# schema_projet_mai_juin_gamestation.net
KiCad netlist of a schematic drawn in Altium Designer
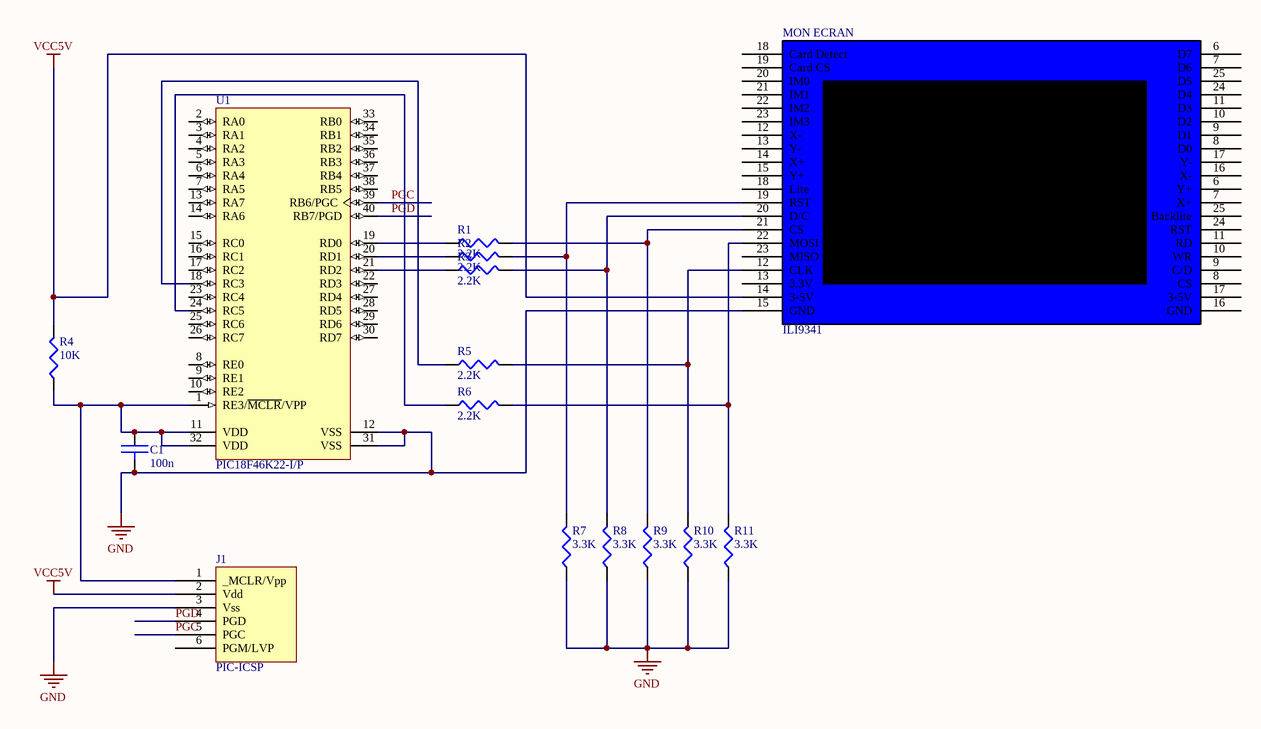
[diagram p0: schema_projet_mai_juin_gamestation.SchDoc]

(export (version "E")
  (design (tool "Eeschema 10.0.6"))
  (components
    (comp (ref "C1")
      (value "100n")
      (footprint "0402")
      (description "capacité non polarisée")
      (fields (field (name "Comment") "CAP"))
      (libsource (lib "ISEN_basics_15-02-2023") (part "CAP"))
    )
    (comp (ref "J1")
      (value "PIC-ICSP")
      (footprint "PIC-ICSP")
      (libsource (lib "ISEN_basics_15-02-2023") (part "PIC-ICSP"))
    )
    (comp (ref "MON ECRAN")
      (value "ILI9341")
      (libsource (lib "schema_ecran_ILI9341_Adafruit") (part "Component_1"))
    )
    (comp (ref "R1")
      (value "2.2K")
      (footprint "0201")
      (description "resistance")
      (fields (field (name "Comment") "RES"))
      (libsource (lib "ISEN_basics_15-02-2023") (part "RES"))
    )
    (comp (ref "R2")
      (value "2.2K")
      (footprint "0201")
      (description "resistance")
      (fields (field (name "Comment") "RES"))
      (libsource (lib "ISEN_basics_15-02-2023") (part "RES"))
    )
    (comp (ref "R3")
      (value "2.2K")
      (footprint "0201")
      (description "resistance")
      (fields (field (name "Comment") "RES"))
      (libsource (lib "ISEN_basics_15-02-2023") (part "RES"))
    )
    (comp (ref "R4")
      (value "10K")
      (footprint "0201")
      (description "resistance")
      (fields (field (name "Comment") "RES"))
      (libsource (lib "ISEN_basics_15-02-2023") (part "RES"))
    )
    (comp (ref "R5")
      (value "2.2K")
      (footprint "0201")
      (description "resistance")
      (fields (field (name "Comment") "RES"))
      (libsource (lib "ISEN_basics_15-02-2023") (part "RES"))
    )
    (comp (ref "R6")
      (value "2.2K")
      (footprint "0201")
      (description "resistance")
      (fields (field (name "Comment") "RES"))
      (libsource (lib "ISEN_basics_15-02-2023") (part "RES"))
    )
    (comp (ref "R7")
      (value "3.3K")
      (footprint "0201")
      (description "resistance")
      (fields (field (name "Comment") "RES"))
      (libsource (lib "ISEN_basics_15-02-2023") (part "RES"))
    )
    (comp (ref "R8")
      (value "3.3K")
      (footprint "0201")
      (description "resistance")
      (fields (field (name "Comment") "RES"))
      (libsource (lib "ISEN_basics_15-02-2023") (part "RES"))
    )
    (comp (ref "R9")
      (value "3.3K")
      (footprint "0201")
      (description "resistance")
      (fields (field (name "Comment") "RES"))
      (libsource (lib "ISEN_basics_15-02-2023") (part "RES"))
    )
    (comp (ref "R10")
      (value "3.3K")
      (footprint "0201")
      (description "resistance")
      (fields (field (name "Comment") "RES"))
      (libsource (lib "ISEN_basics_15-02-2023") (part "RES"))
    )
    (comp (ref "R11")
      (value "3.3K")
      (footprint "0201")
      (description "resistance")
      (fields (field (name "Comment") "RES"))
      (libsource (lib "ISEN_basics_15-02-2023") (part "RES"))
    )
    (comp (ref "U1")
      (value "PIC18F46K22-I/P")
      (footprint "MCHP-PDIP-P40")
      (fields (field (name "MANUFACTURER") "Microchip"))
      (libsource (lib "Microchip PIC18") (part "PIC18F46K22-I/P"))
    )
  )
  (nets
    (net (code "1") (name "/PGC") (class "Default")
      (node (ref "J1") (pin "5") (pinfunction "PGC_5") (pintype "passive"))
      (node (ref "U1") (pin "39") (pinfunction "RB6/PGC_39") (pintype "bidirectional"))
    )
    (net (code "2") (name "/PGD") (class "Default")
      (node (ref "J1") (pin "4") (pinfunction "PGD_4") (pintype "passive"))
      (node (ref "U1") (pin "40") (pinfunction "RB7/PGD_40") (pintype "bidirectional"))
    )
    (net (code "3") (name "GND") (class "Default")
      (node (ref "C1") (pin "2") (pinfunction "2_2") (pintype "passive"))
      (node (ref "J1") (pin "3") (pinfunction "Vss_3") (pintype "passive"))
      (node (ref "MON ECRAN") (pin "15") (pinfunction "GND_15") (pintype "passive"))
      (node (ref "R10") (pin "1") (pintype "passive"))
      (node (ref "R11") (pin "1") (pintype "passive"))
      (node (ref "R7") (pin "1") (pintype "passive"))
      (node (ref "R8") (pin "1") (pintype "passive"))
      (node (ref "R9") (pin "1") (pintype "passive"))
      (node (ref "U1") (pin "12") (pinfunction "VSS_12") (pintype "power_in"))
      (node (ref "U1") (pin "31") (pinfunction "VSS_31") (pintype "power_in"))
    )
    (net (code "4") (name "Net-(J1-_MCLR{slash}Vpp)") (class "Default")
      (node (ref "C1") (pin "1") (pinfunction "1_1") (pintype "passive"))
      (node (ref "J1") (pin "1") (pinfunction "_MCLR/Vpp_1") (pintype "passive"))
      (node (ref "R4") (pin "1") (pintype "passive"))
      (node (ref "U1") (pin "1") (pinfunction "RE3/~{MCLR}/VPP_1") (pintype "input"))
      (node (ref "U1") (pin "11") (pinfunction "VDD_11") (pintype "power_in"))
      (node (ref "U1") (pin "32") (pinfunction "VDD_32") (pintype "power_in"))
    )
    (net (code "5") (name "Net-(MON ECRAN-CLK)") (class "Default")
      (node (ref "MON ECRAN") (pin "12") (pinfunction "CLK_12") (pintype "passive"))
      (node (ref "R10") (pin "2") (pintype "passive"))
      (node (ref "R5") (pin "2") (pintype "passive"))
    )
    (net (code "6") (name "Net-(MON ECRAN-CS-Pad21)") (class "Default")
      (node (ref "MON ECRAN") (pin "21") (pinfunction "CS_21") (pintype "passive"))
      (node (ref "R1") (pin "2") (pintype "passive"))
      (node (ref "R9") (pin "2") (pintype "passive"))
    )
    (net (code "7") (name "Net-(MON ECRAN-D{slash}C)") (class "Default")
      (node (ref "MON ECRAN") (pin "20") (pinfunction "D/C_20") (pintype "passive"))
      (node (ref "R3") (pin "2") (pintype "passive"))
      (node (ref "R8") (pin "2") (pintype "passive"))
    )
    (net (code "8") (name "Net-(MON ECRAN-MOSI)") (class "Default")
      (node (ref "MON ECRAN") (pin "22") (pinfunction "MOSI_22") (pintype "passive"))
      (node (ref "R11") (pin "2") (pintype "passive"))
      (node (ref "R6") (pin "2") (pintype "passive"))
    )
    (net (code "9") (name "Net-(MON ECRAN-RST-Pad19)") (class "Default")
      (node (ref "MON ECRAN") (pin "19") (pinfunction "RST_19") (pintype "passive"))
      (node (ref "R2") (pin "2") (pintype "passive"))
      (node (ref "R7") (pin "2") (pintype "passive"))
    )
    (net (code "10") (name "Net-(U1-RC3)") (class "Default")
      (node (ref "R5") (pin "1") (pintype "passive"))
      (node (ref "U1") (pin "18") (pinfunction "RC3_18") (pintype "bidirectional"))
    )
    (net (code "11") (name "Net-(U1-RC5)") (class "Default")
      (node (ref "R6") (pin "1") (pintype "passive"))
      (node (ref "U1") (pin "24") (pinfunction "RC5_24") (pintype "bidirectional"))
    )
    (net (code "12") (name "Net-(U1-RD0)") (class "Default")
      (node (ref "R1") (pin "1") (pintype "passive"))
      (node (ref "U1") (pin "19") (pinfunction "RD0_19") (pintype "bidirectional"))
    )
    (net (code "13") (name "Net-(U1-RD1)") (class "Default")
      (node (ref "R2") (pin "1") (pintype "passive"))
      (node (ref "U1") (pin "20") (pinfunction "RD1_20") (pintype "bidirectional"))
    )
    (net (code "14") (name "Net-(U1-RD2)") (class "Default")
      (node (ref "R3") (pin "1") (pintype "passive"))
      (node (ref "U1") (pin "21") (pinfunction "RD2_21") (pintype "bidirectional"))
    )
    (net (code "15") (name "VCC5V") (class "Default")
      (node (ref "J1") (pin "2") (pinfunction "Vdd_2") (pintype "passive"))
      (node (ref "MON ECRAN") (pin "14") (pinfunction "3-5V_14") (pintype "passive"))
      (node (ref "R4") (pin "2") (pintype "passive"))
    )
    (net (code "16") (name "unconnected-(J1-PGM{slash}LVP-Pad6)") (class "Default")
      (node (ref "J1") (pin "6") (pinfunction "PGM/LVP_6") (pintype "passive"))
    )
    (net (code "17") (name "unconnected-(MON ECRAN-3-5V-Pad17)") (class "Default")
      (node (ref "MON ECRAN") (pin "17") (pinfunction "3-5V_17") (pintype "passive"))
    )
    (net (code "18") (name "unconnected-(MON ECRAN-3.3V-Pad13)") (class "Default")
      (node (ref "MON ECRAN") (pin "13") (pinfunction "3.3V_13") (pintype "passive"))
    )
    (net (code "19") (name "unconnected-(MON ECRAN-Backlite-Pad25)") (class "Default")
      (node (ref "MON ECRAN") (pin "25") (pinfunction "Backlite_25") (pintype "passive"))
    )
    (net (code "20") (name "unconnected-(MON ECRAN-CS-Pad8)") (class "Default")
      (node (ref "MON ECRAN") (pin "8") (pinfunction "CS_8") (pintype "passive"))
    )
    (net (code "21") (name "unconnected-(MON ECRAN-Card_CS-Pad19)") (class "Default")
      (node (ref "MON ECRAN") (pin "19") (pinfunction "Card_CS_19") (pintype "passive"))
    )
    (net (code "22") (name "unconnected-(MON ECRAN-Card_Detect-Pad18)") (class "Default")
      (node (ref "MON ECRAN") (pin "18") (pinfunction "Card_Detect_18") (pintype "passive"))
    )
    (net (code "23") (name "unconnected-(MON ECRAN-C{slash}D-Pad9)") (class "Default")
      (node (ref "MON ECRAN") (pin "9") (pinfunction "C/D_9") (pintype "passive"))
    )
    (net (code "24") (name "unconnected-(MON ECRAN-D0-Pad8)") (class "Default")
      (node (ref "MON ECRAN") (pin "8") (pinfunction "D0_8") (pintype "passive"))
    )
    (net (code "25") (name "unconnected-(MON ECRAN-D1-Pad9)") (class "Default")
      (node (ref "MON ECRAN") (pin "9") (pinfunction "D1_9") (pintype "passive"))
    )
    (net (code "26") (name "unconnected-(MON ECRAN-D2-Pad10)") (class "Default")
      (node (ref "MON ECRAN") (pin "10") (pinfunction "D2_10") (pintype "passive"))
    )
    (net (code "27") (name "unconnected-(MON ECRAN-D3-Pad11)") (class "Default")
      (node (ref "MON ECRAN") (pin "11") (pinfunction "D3_11") (pintype "passive"))
    )
    (net (code "28") (name "unconnected-(MON ECRAN-D4-Pad24)") (class "Default")
      (node (ref "MON ECRAN") (pin "24") (pinfunction "D4_24") (pintype "passive"))
    )
    (net (code "29") (name "unconnected-(MON ECRAN-D5-Pad25)") (class "Default")
      (node (ref "MON ECRAN") (pin "25") (pinfunction "D5_25") (pintype "passive"))
    )
    (net (code "30") (name "unconnected-(MON ECRAN-D6-Pad7)") (class "Default")
      (node (ref "MON ECRAN") (pin "7") (pinfunction "D6_7") (pintype "passive"))
    )
    (net (code "31") (name "unconnected-(MON ECRAN-D7-Pad6)") (class "Default")
      (node (ref "MON ECRAN") (pin "6") (pinfunction "D7_6") (pintype "passive"))
    )
    (net (code "32") (name "unconnected-(MON ECRAN-GND-Pad16)") (class "Default")
      (node (ref "MON ECRAN") (pin "16") (pinfunction "GND_16") (pintype "passive"))
    )
    (net (code "33") (name "unconnected-(MON ECRAN-IM0-Pad20)") (class "Default")
      (node (ref "MON ECRAN") (pin "20") (pinfunction "IM0_20") (pintype "passive"))
    )
    (net (code "34") (name "unconnected-(MON ECRAN-IM1-Pad21)") (class "Default")
      (node (ref "MON ECRAN") (pin "21") (pinfunction "IM1_21") (pintype "passive"))
    )
    (net (code "35") (name "unconnected-(MON ECRAN-IM2-Pad22)") (class "Default")
      (node (ref "MON ECRAN") (pin "22") (pinfunction "IM2_22") (pintype "passive"))
    )
    (net (code "36") (name "unconnected-(MON ECRAN-IM3-Pad23)") (class "Default")
      (node (ref "MON ECRAN") (pin "23") (pinfunction "IM3_23") (pintype "passive"))
    )
    (net (code "37") (name "unconnected-(MON ECRAN-Lite-Pad18)") (class "Default")
      (node (ref "MON ECRAN") (pin "18") (pinfunction "Lite_18") (pintype "passive"))
    )
    (net (code "38") (name "unconnected-(MON ECRAN-MISO-Pad23)") (class "Default")
      (node (ref "MON ECRAN") (pin "23") (pinfunction "MISO_23") (pintype "passive"))
    )
    (net (code "39") (name "unconnected-(MON ECRAN-RD-Pad11)") (class "Default")
      (node (ref "MON ECRAN") (pin "11") (pinfunction "RD_11") (pintype "passive"))
    )
    (net (code "40") (name "unconnected-(MON ECRAN-RST-Pad24)") (class "Default")
      (node (ref "MON ECRAN") (pin "24") (pinfunction "RST_24") (pintype "passive"))
    )
    (net (code "41") (name "unconnected-(MON ECRAN-WR-Pad10)") (class "Default")
      (node (ref "MON ECRAN") (pin "10") (pinfunction "WR_10") (pintype "passive"))
    )
    (net (code "42") (name "unconnected-(MON ECRAN-X+-Pad7)") (class "Default")
      (node (ref "MON ECRAN") (pin "7") (pinfunction "X+_7") (pintype "passive"))
    )
    (net (code "43") (name "unconnected-(MON ECRAN-X+-Pad14)") (class "Default")
      (node (ref "MON ECRAN") (pin "14") (pinfunction "X+_14") (pintype "passive"))
    )
    (net (code "44") (name "unconnected-(MON ECRAN-X--Pad12)") (class "Default")
      (node (ref "MON ECRAN") (pin "12") (pinfunction "X-_12") (pintype "passive"))
    )
    (net (code "45") (name "unconnected-(MON ECRAN-X--Pad16)") (class "Default")
      (node (ref "MON ECRAN") (pin "16") (pinfunction "X-_16") (pintype "passive"))
    )
    (net (code "46") (name "unconnected-(MON ECRAN-Y+-Pad6)") (class "Default")
      (node (ref "MON ECRAN") (pin "6") (pinfunction "Y+_6") (pintype "passive"))
    )
    (net (code "47") (name "unconnected-(MON ECRAN-Y+-Pad15)") (class "Default")
      (node (ref "MON ECRAN") (pin "15") (pinfunction "Y+_15") (pintype "passive"))
    )
    (net (code "48") (name "unconnected-(MON ECRAN-Y--Pad13)") (class "Default")
      (node (ref "MON ECRAN") (pin "13") (pinfunction "Y-_13") (pintype "passive"))
    )
    (net (code "49") (name "unconnected-(MON ECRAN-Y--Pad17)") (class "Default")
      (node (ref "MON ECRAN") (pin "17") (pinfunction "Y-_17") (pintype "passive"))
    )
    (net (code "50") (name "unconnected-(U1-RA0-Pad2)") (class "Default")
      (node (ref "U1") (pin "2") (pinfunction "RA0_2") (pintype "bidirectional"))
    )
    (net (code "51") (name "unconnected-(U1-RA1-Pad3)") (class "Default")
      (node (ref "U1") (pin "3") (pinfunction "RA1_3") (pintype "bidirectional"))
    )
    (net (code "52") (name "unconnected-(U1-RA2-Pad4)") (class "Default")
      (node (ref "U1") (pin "4") (pinfunction "RA2_4") (pintype "bidirectional"))
    )
    (net (code "53") (name "unconnected-(U1-RA3-Pad5)") (class "Default")
      (node (ref "U1") (pin "5") (pinfunction "RA3_5") (pintype "bidirectional"))
    )
    (net (code "54") (name "unconnected-(U1-RA4-Pad6)") (class "Default")
      (node (ref "U1") (pin "6") (pinfunction "RA4_6") (pintype "bidirectional"))
    )
    (net (code "55") (name "unconnected-(U1-RA5-Pad7)") (class "Default")
      (node (ref "U1") (pin "7") (pinfunction "RA5_7") (pintype "bidirectional"))
    )
    (net (code "56") (name "unconnected-(U1-RA6-Pad14)") (class "Default")
      (node (ref "U1") (pin "14") (pinfunction "RA6_14") (pintype "bidirectional"))
    )
    (net (code "57") (name "unconnected-(U1-RA7-Pad13)") (class "Default")
      (node (ref "U1") (pin "13") (pinfunction "RA7_13") (pintype "bidirectional"))
    )
    (net (code "58") (name "unconnected-(U1-RB0-Pad33)") (class "Default")
      (node (ref "U1") (pin "33") (pinfunction "RB0_33") (pintype "bidirectional"))
    )
    (net (code "59") (name "unconnected-(U1-RB1-Pad34)") (class "Default")
      (node (ref "U1") (pin "34") (pinfunction "RB1_34") (pintype "bidirectional"))
    )
    (net (code "60") (name "unconnected-(U1-RB2-Pad35)") (class "Default")
      (node (ref "U1") (pin "35") (pinfunction "RB2_35") (pintype "bidirectional"))
    )
    (net (code "61") (name "unconnected-(U1-RB3-Pad36)") (class "Default")
      (node (ref "U1") (pin "36") (pinfunction "RB3_36") (pintype "bidirectional"))
    )
    (net (code "62") (name "unconnected-(U1-RB4-Pad37)") (class "Default")
      (node (ref "U1") (pin "37") (pinfunction "RB4_37") (pintype "bidirectional"))
    )
    (net (code "63") (name "unconnected-(U1-RB5-Pad38)") (class "Default")
      (node (ref "U1") (pin "38") (pinfunction "RB5_38") (pintype "bidirectional"))
    )
    (net (code "64") (name "unconnected-(U1-RC0-Pad15)") (class "Default")
      (node (ref "U1") (pin "15") (pinfunction "RC0_15") (pintype "bidirectional"))
    )
    (net (code "65") (name "unconnected-(U1-RC1-Pad16)") (class "Default")
      (node (ref "U1") (pin "16") (pinfunction "RC1_16") (pintype "bidirectional"))
    )
    (net (code "66") (name "unconnected-(U1-RC2-Pad17)") (class "Default")
      (node (ref "U1") (pin "17") (pinfunction "RC2_17") (pintype "bidirectional"))
    )
    (net (code "67") (name "unconnected-(U1-RC4-Pad23)") (class "Default")
      (node (ref "U1") (pin "23") (pinfunction "RC4_23") (pintype "bidirectional"))
    )
    (net (code "68") (name "unconnected-(U1-RC6-Pad25)") (class "Default")
      (node (ref "U1") (pin "25") (pinfunction "RC6_25") (pintype "bidirectional"))
    )
    (net (code "69") (name "unconnected-(U1-RC7-Pad26)") (class "Default")
      (node (ref "U1") (pin "26") (pinfunction "RC7_26") (pintype "bidirectional"))
    )
    (net (code "70") (name "unconnected-(U1-RD3-Pad22)") (class "Default")
      (node (ref "U1") (pin "22") (pinfunction "RD3_22") (pintype "bidirectional"))
    )
    (net (code "71") (name "unconnected-(U1-RD4-Pad27)") (class "Default")
      (node (ref "U1") (pin "27") (pinfunction "RD4_27") (pintype "bidirectional"))
    )
    (net (code "72") (name "unconnected-(U1-RD5-Pad28)") (class "Default")
      (node (ref "U1") (pin "28") (pinfunction "RD5_28") (pintype "bidirectional"))
    )
    (net (code "73") (name "unconnected-(U1-RD6-Pad29)") (class "Default")
      (node (ref "U1") (pin "29") (pinfunction "RD6_29") (pintype "bidirectional"))
    )
    (net (code "74") (name "unconnected-(U1-RD7-Pad30)") (class "Default")
      (node (ref "U1") (pin "30") (pinfunction "RD7_30") (pintype "bidirectional"))
    )
    (net (code "75") (name "unconnected-(U1-RE0-Pad8)") (class "Default")
      (node (ref "U1") (pin "8") (pinfunction "RE0_8") (pintype "bidirectional"))
    )
    (net (code "76") (name "unconnected-(U1-RE1-Pad9)") (class "Default")
      (node (ref "U1") (pin "9") (pinfunction "RE1_9") (pintype "bidirectional"))
    )
    (net (code "77") (name "unconnected-(U1-RE2-Pad10)") (class "Default")
      (node (ref "U1") (pin "10") (pinfunction "RE2_10") (pintype "bidirectional"))
    )
  )
)
